# IGresupply1-2.net
KiCad netlist of a schematic drawn in Altium Designer
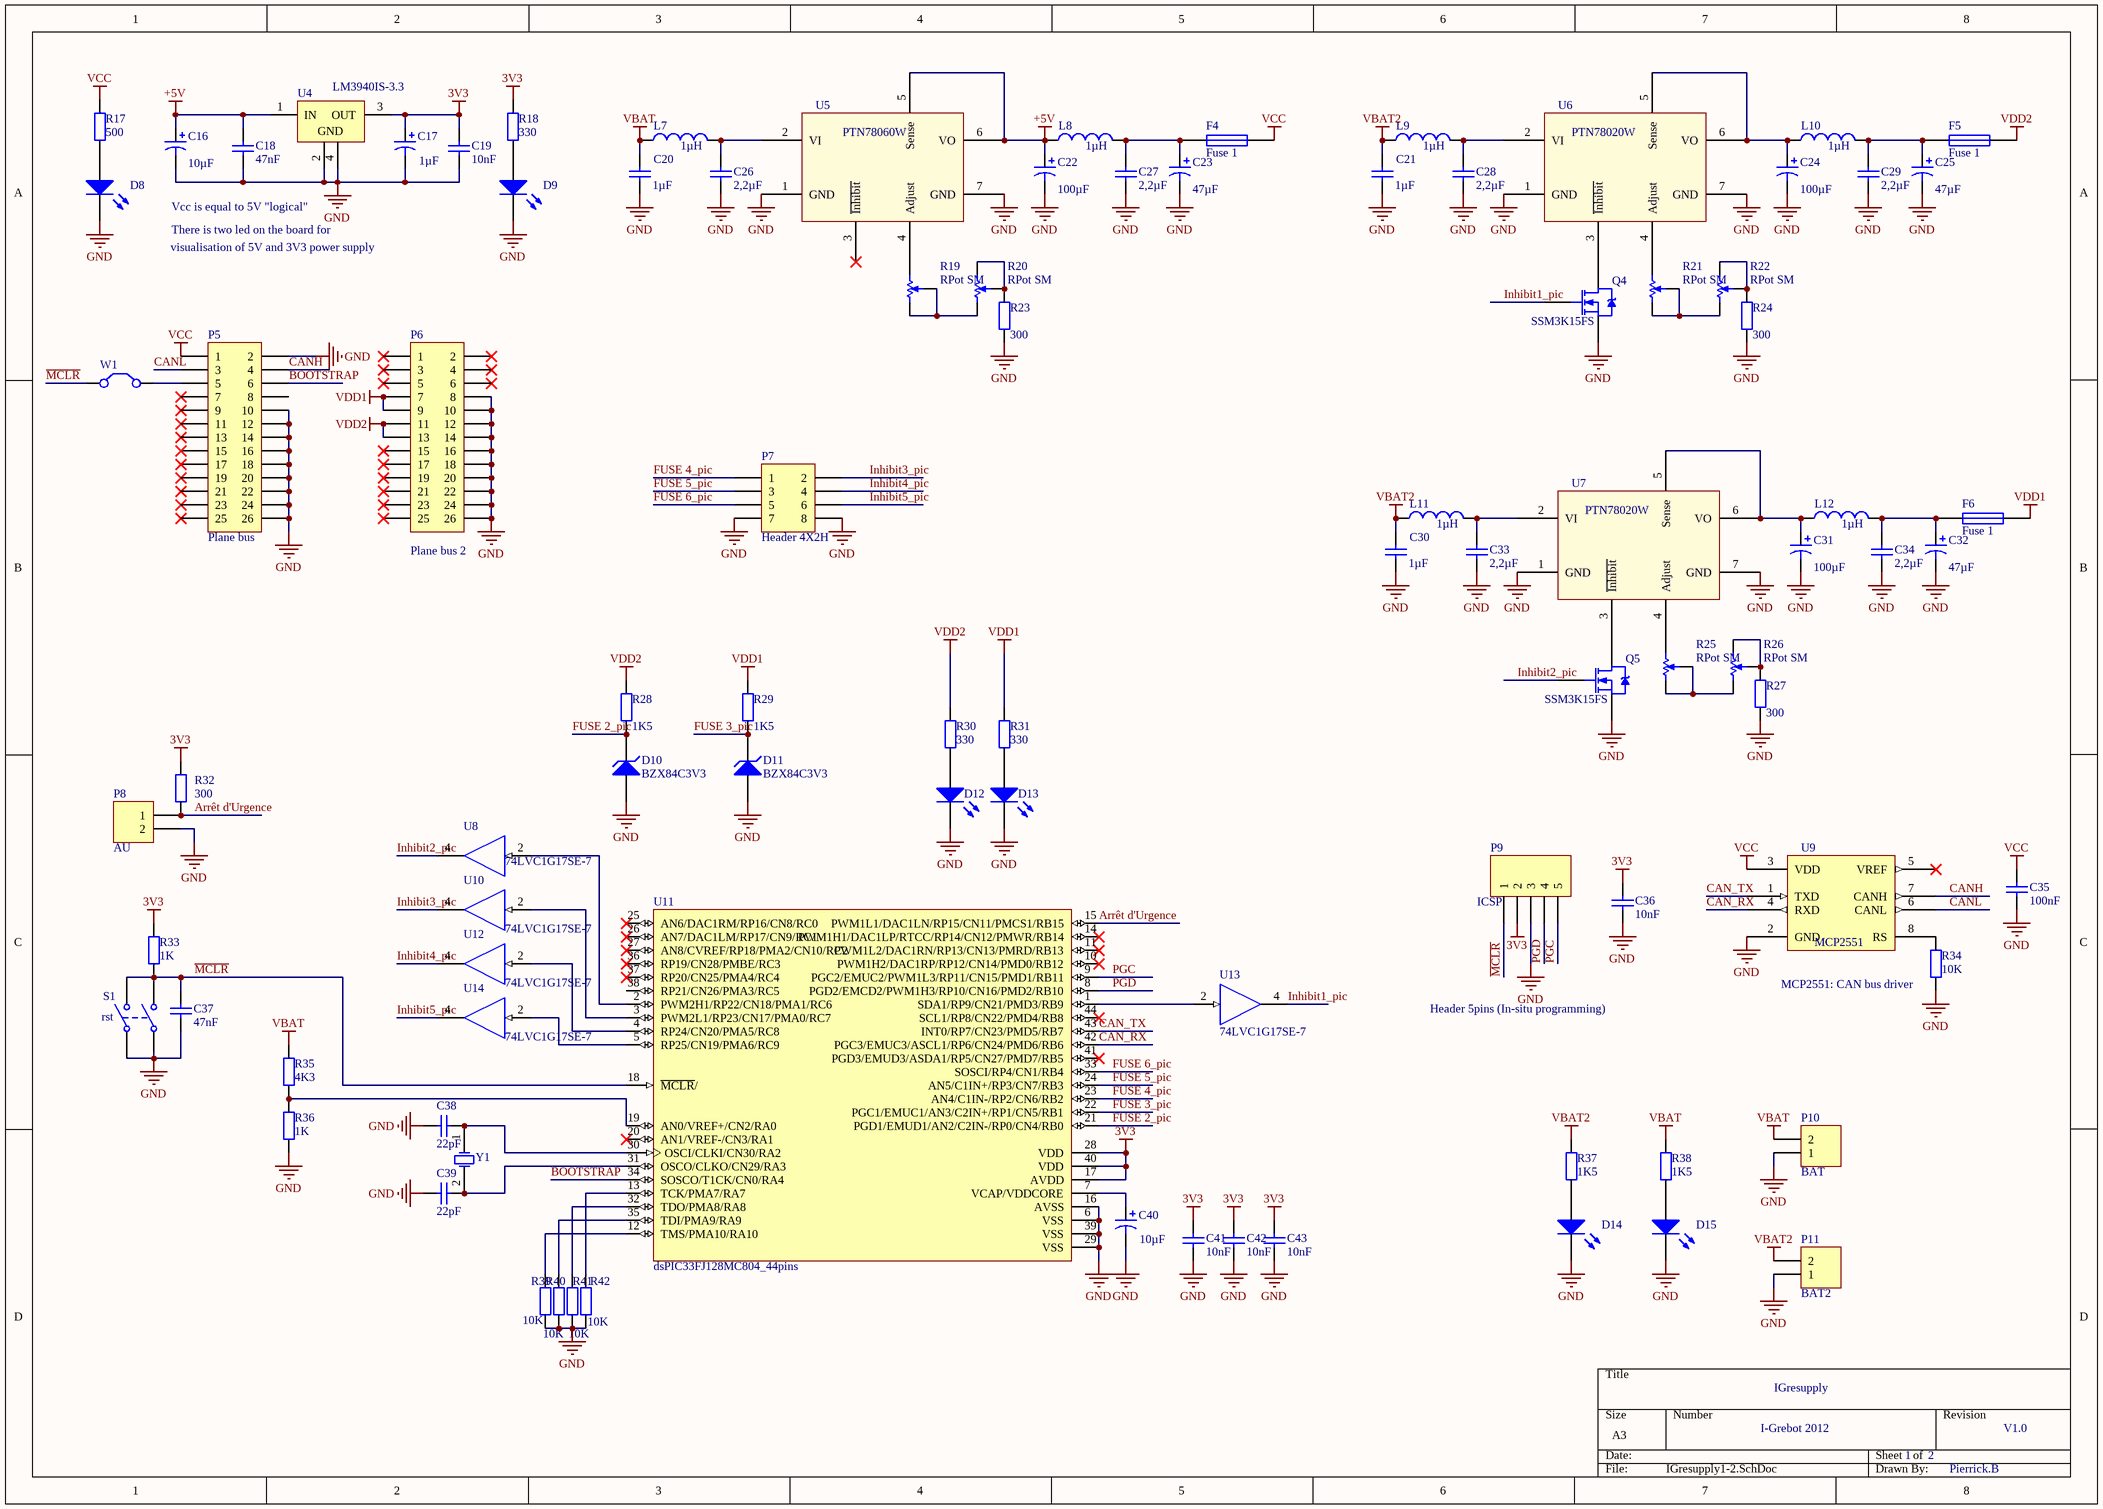
[diagram p0: IGresupply1-2.SchDoc]

(export (version "E")
  (design (tool "Eeschema 10.0.6"))
  (components
    (comp (ref "C16")
      (value "10µF")
      (footprint "Boitier tantale A")
      (description "Polarized Capacitor")
      (fields (field (name "Comment") "Cap Pol") (field (name "PUBLISHER") "Altium Limited"))
      (libsource (lib "I-GREBOT 2009") (part "Cap Pol"))
    )
    (comp (ref "C17")
      (value "1µF")
      (footprint "Boitier tantale A")
      (description "Polarized Capacitor")
      (fields (field (name "Comment") "Cap Pol") (field (name "PUBLISHER") "Altium Limited"))
      (libsource (lib "*") (part "Cap Pol"))
    )
    (comp (ref "C18")
      (value "47nF")
      (footprint "C0603")
      (description "Capacitor")
      (fields (field (name "Comment") "Cap") (field (name "PUBLISHER") "Altium Limited"))
      (libsource (lib "Miscellaneous Devices") (part "Cap"))
    )
    (comp (ref "C19")
      (value "10nF")
      (footprint "C0603")
      (description "Capacitor")
      (fields (field (name "Comment") "Cap") (field (name "PUBLISHER") "Altium Limited"))
      (libsource (lib "Miscellaneous Devices") (part "Cap"))
    )
    (comp (ref "C20")
      (value "1µF")
      (footprint "Boitier tantale A")
      (description "Capacitor")
      (fields (field (name "Comment") "Cap") (field (name "PUBLISHER") "Altium Limited"))
      (libsource (lib "LIBRARY IGREBOT") (part "Cap"))
    )
    (comp (ref "C21")
      (value "1µF")
      (footprint "Boitier tantale A")
      (description "Capacitor")
      (fields (field (name "Comment") "Cap") (field (name "PUBLISHER") "Altium Limited"))
      (libsource (lib "LIBRARY IGREBOT") (part "Cap"))
    )
    (comp (ref "C22")
      (value "100µF")
      (footprint "Boitier tantale C")
      (description "Polarized Capacitor")
      (fields (field (name "Comment") "Cap Pol") (field (name "PUBLISHER") "Altium Limited"))
      (libsource (lib "LIBRARY IGREBOT") (part "Cap Pol"))
    )
    (comp (ref "C23")
      (value "47µF")
      (footprint "Boitier tantale C")
      (description "Polarized Capacitor")
      (fields (field (name "Comment") "Cap Pol") (field (name "PUBLISHER") "Altium Limited"))
      (libsource (lib "LIBRARY IGREBOT") (part "Cap Pol"))
    )
    (comp (ref "C24")
      (value "100µF")
      (footprint "Boitier tantale C")
      (description "Polarized Capacitor")
      (fields (field (name "Comment") "Cap Pol") (field (name "PUBLISHER") "Altium Limited"))
      (libsource (lib "LIBRARY IGREBOT") (part "Cap Pol"))
    )
    (comp (ref "C25")
      (value "47µF")
      (footprint "Boitier tantale C")
      (description "Polarized Capacitor")
      (fields (field (name "Comment") "Cap Pol") (field (name "PUBLISHER") "Altium Limited"))
      (libsource (lib "LIBRARY IGREBOT") (part "Cap Pol"))
    )
    (comp (ref "C26")
      (value "2,2µF")
      (footprint "Boitier tantale A")
      (description "Capacitor")
      (fields (field (name "Comment") "Cap") (field (name "PUBLISHER") "Altium Limited"))
      (libsource (lib "LIBRARY IGREBOT") (part "Cap"))
    )
    (comp (ref "C27")
      (value "2,2µF")
      (footprint "Boitier tantale A")
      (description "Capacitor")
      (fields (field (name "Comment") "Cap") (field (name "PUBLISHER") "Altium Limited"))
      (libsource (lib "LIBRARY IGREBOT") (part "Cap"))
    )
    (comp (ref "C28")
      (value "2,2µF")
      (footprint "Boitier tantale A")
      (description "Capacitor")
      (fields (field (name "Comment") "Cap") (field (name "PUBLISHER") "Altium Limited"))
      (libsource (lib "LIBRARY IGREBOT") (part "Cap"))
    )
    (comp (ref "C29")
      (value "2,2µF")
      (footprint "Boitier tantale A")
      (description "Capacitor")
      (fields (field (name "Comment") "Cap") (field (name "PUBLISHER") "Altium Limited"))
      (libsource (lib "LIBRARY IGREBOT") (part "Cap"))
    )
    (comp (ref "C30")
      (value "1µF")
      (footprint "Boitier tantale A")
      (description "Capacitor")
      (fields (field (name "Comment") "Cap") (field (name "PUBLISHER") "Altium Limited"))
      (libsource (lib "LIBRARY IGREBOT") (part "Cap"))
    )
    (comp (ref "C31")
      (value "100µF")
      (footprint "Boitier tantale C")
      (description "Polarized Capacitor")
      (fields (field (name "Comment") "Cap Pol") (field (name "PUBLISHER") "Altium Limited"))
      (libsource (lib "LIBRARY IGREBOT") (part "Cap Pol"))
    )
    (comp (ref "C32")
      (value "47µF")
      (footprint "Boitier tantale C")
      (description "Polarized Capacitor")
      (fields (field (name "Comment") "Cap Pol") (field (name "PUBLISHER") "Altium Limited"))
      (libsource (lib "LIBRARY IGREBOT") (part "Cap Pol"))
    )
    (comp (ref "C33")
      (value "2,2µF")
      (footprint "Boitier tantale A")
      (description "Capacitor")
      (fields (field (name "Comment") "Cap") (field (name "PUBLISHER") "Altium Limited"))
      (libsource (lib "LIBRARY IGREBOT") (part "Cap"))
    )
    (comp (ref "C34")
      (value "2,2µF")
      (footprint "Boitier tantale A")
      (description "Capacitor")
      (fields (field (name "Comment") "Cap") (field (name "PUBLISHER") "Altium Limited"))
      (libsource (lib "LIBRARY IGREBOT") (part "Cap"))
    )
    (comp (ref "C35")
      (value "100nF")
      (footprint "C0603")
      (description "Capacitor")
      (fields (field (name "Comment") "Cap") (field (name "PUBLISHER") "Altium Limited"))
      (libsource (lib "Miscellaneous Devices") (part "Cap"))
    )
    (comp (ref "C36")
      (value "10nF")
      (footprint "C0603")
      (description "Capacitor")
      (fields (field (name "Comment") "Cap") (field (name "PUBLISHER") "Altium Limited"))
      (libsource (lib "Miscellaneous Devices") (part "Cap"))
    )
    (comp (ref "C37")
      (value "47nF")
      (footprint "C0603")
      (description "Capacitor")
      (fields (field (name "Comment") "Cap") (field (name "PUBLISHER") "Altium Limited"))
      (libsource (lib "Miscellaneous Devices") (part "Cap"))
    )
    (comp (ref "C38")
      (value "22pF")
      (footprint "C0603")
      (description "Capacitor")
      (fields (field (name "Comment") "Cap") (field (name "PUBLISHER") "Altium Limited"))
      (libsource (lib "Miscellaneous Devices") (part "Cap"))
    )
    (comp (ref "C39")
      (value "22pF")
      (footprint "C0603")
      (description "Capacitor")
      (fields (field (name "Comment") "Cap") (field (name "PUBLISHER") "Altium Limited"))
      (libsource (lib "Miscellaneous Devices") (part "Cap"))
    )
    (comp (ref "C40")
      (value "10µF")
      (footprint "Boitier tantale A")
      (description "Polarized Capacitor")
      (fields (field (name "Comment") "Cap Pol") (field (name "PUBLISHER") "Altium Limited"))
      (libsource (lib "*") (part "Cap Pol"))
    )
    (comp (ref "C41")
      (value "10nF")
      (footprint "C0603")
      (description "Capacitor")
      (fields (field (name "Comment") "Cap") (field (name "PUBLISHER") "Altium Limited"))
      (libsource (lib "Miscellaneous Devices") (part "Cap"))
    )
    (comp (ref "C42")
      (value "10nF")
      (footprint "C0603")
      (description "Capacitor")
      (fields (field (name "Comment") "Cap") (field (name "PUBLISHER") "Altium Limited"))
      (libsource (lib "Miscellaneous Devices") (part "Cap"))
    )
    (comp (ref "C43")
      (value "10nF")
      (footprint "C0603")
      (description "Capacitor")
      (fields (field (name "Comment") "Cap") (field (name "PUBLISHER") "Altium Limited"))
      (libsource (lib "Miscellaneous Devices") (part "Cap"))
    )
    (comp (ref "D8")
      (value "LED1")
      (footprint "HSMS-C110")
      (description "Typical RED GaAs LED")
      (fields (field (name "PUBLISHER") "Altium Limited"))
      (libsource (lib "I-GREBOT 2009") (part "LED1"))
    )
    (comp (ref "D9")
      (value "LED1")
      (footprint "HSMS-C110")
      (description "Typical RED GaAs LED")
      (fields (field (name "PUBLISHER") "Altium Limited"))
      (libsource (lib "I-GREBOT 2009") (part "LED1"))
    )
    (comp (ref "D10")
      (value "BZX84C3V3")
      (footprint "SOT-23")
      (description "Zener Diode")
      (fields (field (name "PUBLISHER") "Altium Limited"))
      (libsource (lib "LIBRARY IGREBOT") (part "D Zener"))
    )
    (comp (ref "D11")
      (value "BZX84C3V3")
      (footprint "SOT-23")
      (description "Zener Diode")
      (fields (field (name "PUBLISHER") "Altium Limited"))
      (libsource (lib "LIBRARY IGREBOT") (part "D Zener"))
    )
    (comp (ref "D12")
      (value "LED1")
      (footprint "HSMS-C110")
      (description "Typical RED GaAs LED")
      (fields (field (name "PUBLISHER") "Altium Limited"))
      (libsource (lib "I-GREBOT 2009") (part "LED1"))
    )
    (comp (ref "D13")
      (value "LED1")
      (footprint "HSMS-C110")
      (description "Typical RED GaAs LED")
      (fields (field (name "PUBLISHER") "Altium Limited"))
      (libsource (lib "I-GREBOT 2009") (part "LED1"))
    )
    (comp (ref "D14")
      (value "LED1")
      (footprint "HSMS-C110")
      (description "Typical RED GaAs LED")
      (fields (field (name "PUBLISHER") "Altium Limited"))
      (libsource (lib "I-GREBOT 2009") (part "LED1"))
    )
    (comp (ref "D15")
      (value "LED1")
      (footprint "HSMS-C110")
      (description "Typical RED GaAs LED")
      (fields (field (name "PUBLISHER") "Altium Limited"))
      (libsource (lib "I-GREBOT 2009") (part "LED1"))
    )
    (comp (ref "F4")
      (value "Fuse 1")
      (footprint "MCCQ-122")
      (description "Fuse")
      (fields (field (name "PUBLISHER") "Altium Limited"))
      (libsource (lib "LIBRARY IGREBOT") (part "Fuse 1"))
    )
    (comp (ref "F5")
      (value "Fuse 1")
      (footprint "MCCQ-122")
      (description "Fuse")
      (fields (field (name "PUBLISHER") "Altium Limited"))
      (libsource (lib "LIBRARY IGREBOT") (part "Fuse 1"))
    )
    (comp (ref "F6")
      (value "Fuse 1")
      (footprint "MCCQ-122")
      (description "Fuse")
      (fields (field (name "PUBLISHER") "Altium Limited"))
      (libsource (lib "LIBRARY IGREBOT") (part "Fuse 1"))
    )
    (comp (ref "L7")
      (value "1µH")
      (footprint "744772010")
      (description "Inductor")
      (fields (field (name "PUBLISHER") "Altium Limited"))
      (libsource (lib "LIBRARY IGREBOT") (part "Inductor"))
    )
    (comp (ref "L8")
      (value "1µH")
      (footprint "744772010")
      (description "Inductor")
      (fields (field (name "PUBLISHER") "Altium Limited"))
      (libsource (lib "LIBRARY IGREBOT") (part "Inductor"))
    )
    (comp (ref "L9")
      (value "1µH")
      (footprint "744772010")
      (description "Inductor")
      (fields (field (name "PUBLISHER") "Altium Limited"))
      (libsource (lib "LIBRARY IGREBOT") (part "Inductor"))
    )
    (comp (ref "L10")
      (value "1µH")
      (footprint "744772010")
      (description "Inductor")
      (fields (field (name "PUBLISHER") "Altium Limited"))
      (libsource (lib "LIBRARY IGREBOT") (part "Inductor"))
    )
    (comp (ref "L11")
      (value "1µH")
      (footprint "744772010")
      (description "Inductor")
      (fields (field (name "PUBLISHER") "Altium Limited"))
      (libsource (lib "LIBRARY IGREBOT") (part "Inductor"))
    )
    (comp (ref "L12")
      (value "1µH")
      (footprint "744772010")
      (description "Inductor")
      (fields (field (name "PUBLISHER") "Altium Limited"))
      (libsource (lib "LIBRARY IGREBOT") (part "Inductor"))
    )
    (comp (ref "P5")
      (value "Plane bus")
      (footprint "HDR2X13H")
      (description "Header, 13-Pin, Dual row, Right Angle")
      (fields (field (name "PUBLISHER") "Altium Limited"))
      (libsource (lib "Miscellaneous Connectors") (part "Header 13X2H"))
    )
    (comp (ref "P6")
      (value "Plane bus 2")
      (footprint "HDR2X13H")
      (description "Header, 13-Pin, Dual row, Right Angle")
      (fields (field (name "PUBLISHER") "Altium Limited"))
      (libsource (lib "Miscellaneous Connectors") (part "Header 13X2H"))
    )
    (comp (ref "P7")
      (value "Header 4X2H")
      (footprint "HDR2X4H")
      (description "Header, 4-Pin, Dual row, Right Angle")
      (fields (field (name "PUBLISHER") "Altium Limited"))
      (libsource (lib "Miscellaneous Connectors") (part "Header 4X2H"))
    )
    (comp (ref "P8")
      (value "AU")
      (footprint "SL 5.08/90")
      (description "Micro-Fit, 3.0")
      (fields (field (name "PUBLISHER") "Altium Limited"))
      (libsource (lib "") (part "0436500203_1"))
    )
    (comp (ref "P9")
      (value "ICSP")
      (footprint "HDR1X5")
      (description "Header, 5-Pin")
      (fields (field (name "PUBLISHER") "Altium Limited"))
      (libsource (lib "LIBRARY IGREBOT") (part "Header 5"))
    )
    (comp (ref "P10")
      (value "BAT")
      (footprint "SL 5.08/90")
      (description "Micro-Fit, 3.0")
      (fields (field (name "PUBLISHER") "Altium Limited"))
      (libsource (lib "I-GREBOT 2010") (part "0436500203"))
    )
    (comp (ref "P11")
      (value "BAT2")
      (footprint "SL 5.08/90")
      (description "Micro-Fit, 3.0")
      (fields (field (name "PUBLISHER") "Altium Limited"))
      (libsource (lib "I-GREBOT 2010") (part "0436500203"))
    )
    (comp (ref "Q4")
      (value "SSM3K15FS")
      (footprint "SOT-23")
      (description "N-Channel Power MOSFET")
      (fields (field (name "PUBLISHER") "Altium Limited"))
      (libsource (lib "LIBRARY IGREBOT") (part "NMOS-2"))
    )
    (comp (ref "Q5")
      (value "SSM3K15FS")
      (footprint "SOT-23")
      (description "N-Channel Power MOSFET")
      (fields (field (name "PUBLISHER") "Altium Limited"))
      (libsource (lib "LIBRARY IGREBOT") (part "NMOS-2"))
    )
    (comp (ref "R17")
      (value "500")
      (footprint "0805")
      (description "Resistor")
      (fields (field (name "Comment") "Res2") (field (name "PUBLISHER") "Altium Limited"))
      (libsource (lib "*") (part "Res2"))
    )
    (comp (ref "R18")
      (value "330")
      (footprint "0805")
      (description "Resistor")
      (fields (field (name "Comment") "Res2") (field (name "PUBLISHER") "Altium Limited"))
      (libsource (lib "*") (part "Res2"))
    )
    (comp (ref "R19")
      (value "RPot SM")
      (footprint "3296X")
      (description "Square Trimming Potentiometer")
      (fields (field (name "PUBLISHER") "Altium Limited"))
      (libsource (lib "LIBRARY IGREBOT") (part "RPot SM"))
    )
    (comp (ref "R20")
      (value "RPot SM")
      (footprint "3296X")
      (description "Square Trimming Potentiometer")
      (fields (field (name "PUBLISHER") "Altium Limited"))
      (libsource (lib "LIBRARY IGREBOT") (part "RPot SM"))
    )
    (comp (ref "R21")
      (value "RPot SM")
      (footprint "3296X")
      (description "Square Trimming Potentiometer")
      (fields (field (name "PUBLISHER") "Altium Limited"))
      (libsource (lib "LIBRARY IGREBOT") (part "RPot SM"))
    )
    (comp (ref "R22")
      (value "RPot SM")
      (footprint "3296X")
      (description "Square Trimming Potentiometer")
      (fields (field (name "PUBLISHER") "Altium Limited"))
      (libsource (lib "LIBRARY IGREBOT") (part "RPot SM"))
    )
    (comp (ref "R23")
      (value "300")
      (footprint "0805")
      (description "Resistor")
      (fields (field (name "Comment") "Res2") (field (name "PUBLISHER") "Altium Limited"))
      (libsource (lib "LIBRARY IGREBOT") (part "Res2"))
    )
    (comp (ref "R24")
      (value "300")
      (footprint "0805")
      (description "Resistor")
      (fields (field (name "Comment") "Res2") (field (name "PUBLISHER") "Altium Limited"))
      (libsource (lib "LIBRARY IGREBOT") (part "Res2"))
    )
    (comp (ref "R25")
      (value "RPot SM")
      (footprint "3296X")
      (description "Square Trimming Potentiometer")
      (fields (field (name "PUBLISHER") "Altium Limited"))
      (libsource (lib "LIBRARY IGREBOT") (part "RPot SM"))
    )
    (comp (ref "R26")
      (value "RPot SM")
      (footprint "3296X")
      (description "Square Trimming Potentiometer")
      (fields (field (name "PUBLISHER") "Altium Limited"))
      (libsource (lib "LIBRARY IGREBOT") (part "RPot SM"))
    )
    (comp (ref "R27")
      (value "300")
      (footprint "0805")
      (description "Resistor")
      (fields (field (name "Comment") "Res2") (field (name "PUBLISHER") "Altium Limited"))
      (libsource (lib "LIBRARY IGREBOT") (part "Res2"))
    )
    (comp (ref "R28")
      (value "1K5")
      (footprint "0805")
      (description "Resistor")
      (fields (field (name "Comment") "Res2") (field (name "PUBLISHER") "Altium Limited"))
      (libsource (lib "LIBRARY IGREBOT") (part "Res2"))
    )
    (comp (ref "R29")
      (value "1K5")
      (footprint "0805")
      (description "Resistor")
      (fields (field (name "Comment") "Res2") (field (name "PUBLISHER") "Altium Limited"))
      (libsource (lib "LIBRARY IGREBOT") (part "Res2"))
    )
    (comp (ref "R30")
      (value "330")
      (footprint "0805")
      (description "Resistor")
      (fields (field (name "Comment") "Res2") (field (name "PUBLISHER") "Altium Limited"))
      (libsource (lib "*") (part "Res2"))
    )
    (comp (ref "R31")
      (value "330")
      (footprint "0805")
      (description "Resistor")
      (fields (field (name "Comment") "Res2") (field (name "PUBLISHER") "Altium Limited"))
      (libsource (lib "*") (part "Res2"))
    )
    (comp (ref "R32")
      (value "300")
      (footprint "0603")
      (description "Resistor")
      (fields (field (name "Comment") "Res2") (field (name "PUBLISHER") "Altium Limited"))
      (libsource (lib "LIBRARY IGREBOT") (part "Res2"))
    )
    (comp (ref "R33")
      (value "1K")
      (footprint "0603")
      (description "Resistor")
      (fields (field (name "Comment") "Res2") (field (name "PUBLISHER") "Altium Limited"))
      (libsource (lib "*") (part "Res2"))
    )
    (comp (ref "R34")
      (value "10K")
      (footprint "0805")
      (description "Resistor")
      (fields (field (name "Comment") "Res2") (field (name "PUBLISHER") "Altium Limited"))
      (libsource (lib "") (part "Res2_1"))
    )
    (comp (ref "R35")
      (value "4K3")
      (footprint "0603")
      (description "Resistor")
      (fields (field (name "Comment") "Res2") (field (name "PUBLISHER") "Altium Limited"))
      (libsource (lib "*") (part "Res2"))
    )
    (comp (ref "R36")
      (value "1K")
      (footprint "0603")
      (description "Resistor")
      (fields (field (name "Comment") "Res2") (field (name "PUBLISHER") "Altium Limited"))
      (libsource (lib "*") (part "Res2"))
    )
    (comp (ref "R37")
      (value "1K5")
      (footprint "0805")
      (description "Resistor")
      (fields (field (name "Comment") "Res2") (field (name "PUBLISHER") "Altium Limited"))
      (libsource (lib "*") (part "Res2"))
    )
    (comp (ref "R38")
      (value "1K5")
      (footprint "0805")
      (description "Resistor")
      (fields (field (name "Comment") "Res2") (field (name "PUBLISHER") "Altium Limited"))
      (libsource (lib "*") (part "Res2"))
    )
    (comp (ref "R39")
      (value "10K")
      (footprint "0603")
      (description "Resistor")
      (fields (field (name "Comment") "Res2") (field (name "PUBLISHER") "Altium Limited"))
      (libsource (lib "*") (part "Res2"))
    )
    (comp (ref "R40")
      (value "10K")
      (footprint "0603")
      (description "Resistor")
      (fields (field (name "Comment") "Res2") (field (name "PUBLISHER") "Altium Limited"))
      (libsource (lib "*") (part "Res2"))
    )
    (comp (ref "R41")
      (value "10K")
      (footprint "0603")
      (description "Resistor")
      (fields (field (name "Comment") "Res2") (field (name "PUBLISHER") "Altium Limited"))
      (libsource (lib "*") (part "Res2"))
    )
    (comp (ref "R42")
      (value "10K")
      (footprint "0603")
      (description "Resistor")
      (fields (field (name "Comment") "Res2") (field (name "PUBLISHER") "Altium Limited"))
      (libsource (lib "*") (part "Res2"))
    )
    (comp (ref "S1")
      (value "rst")
      (footprint "Bouton poussoir")
      (description "Double-Pole, Single-Throw Switch")
      (fields (field (name "PUBLISHER") "Altium Limited"))
      (libsource (lib "*") (part "SW-DPST"))
    )
    (comp (ref "U4")
      (value "LM3940IS-3.3")
      (footprint "SOT223")
      (description "1A Low-Dropout Regulator For 5V to 3.3V Conversion")
      (fields (field (name "PUBLISHER") "Altium Limited"))
      (libsource (lib "I-GREBOT 2009") (part "LM3940IS-3.3"))
    )
    (comp (ref "U5")
      (value "PTN78060W")
      (footprint "EUW")
      (libsource (lib "LIBRARY IGREBOT") (part "PTN78060W"))
    )
    (comp (ref "U6")
      (value "PTN78020W")
      (footprint "EUK")
      (libsource (lib "LIBRARY IGREBOT") (part "PTN78020W"))
    )
    (comp (ref "U7")
      (value "PTN78020W")
      (footprint "EUK")
      (libsource (lib "LIBRARY IGREBOT") (part "PTN78020W"))
    )
    (comp (ref "U8")
      (value "74LVC1G17SE-7")
      (footprint "DBV")
      (description "SINGLE BUS BUFFER GATE  WITH 3-STATE OUTPUT")
      (fields (field (name "PUBLISHER") "Altium Limited"))
      (libsource (lib "LIBRARY IGREBOT") (part "74LVC1G17SE-7"))
    )
    (comp (ref "U9")
      (value "MCP2551")
      (footprint "SOIC150-8")
      (description "High Speed Can Transceiver")
      (fields (field (name "PUBLISHER") "Altium Limited"))
      (libsource (lib "*") (part "MCP2551"))
    )
    (comp (ref "U10")
      (value "74LVC1G17SE-7")
      (footprint "DBV")
      (description "SINGLE BUS BUFFER GATE  WITH 3-STATE OUTPUT")
      (fields (field (name "PUBLISHER") "Altium Limited"))
      (libsource (lib "LIBRARY IGREBOT") (part "74LVC1G17SE-7"))
    )
    (comp (ref "U11")
      (value "dsPIC33FJ128MC804_44pins")
      (footprint "TQFP-44")
      (libsource (lib "I-GREBOT 2009") (part "dsPIC33FJ128MC804_44pins"))
    )
    (comp (ref "U12")
      (value "74LVC1G17SE-7")
      (footprint "DBV")
      (description "SINGLE BUS BUFFER GATE  WITH 3-STATE OUTPUT")
      (fields (field (name "PUBLISHER") "Altium Limited"))
      (libsource (lib "LIBRARY IGREBOT") (part "74LVC1G17SE-7"))
    )
    (comp (ref "U13")
      (value "74LVC1G17SE-7")
      (footprint "DBV")
      (description "SINGLE BUS BUFFER GATE  WITH 3-STATE OUTPUT")
      (fields (field (name "PUBLISHER") "Altium Limited"))
      (libsource (lib "LIBRARY IGREBOT") (part "74LVC1G17SE-7"))
    )
    (comp (ref "U14")
      (value "74LVC1G17SE-7")
      (footprint "DBV")
      (description "SINGLE BUS BUFFER GATE  WITH 3-STATE OUTPUT")
      (fields (field (name "PUBLISHER") "Altium Limited"))
      (libsource (lib "LIBRARY IGREBOT") (part "74LVC1G17SE-7"))
    )
    (comp (ref "W1")
      (value "Jumper")
      (footprint "HDR1X2")
      (description "Jumper Wire")
      (fields (field (name "PUBLISHER") "Altium Limited"))
      (libsource (lib "LIBRARY IGREBOT") (part "Jumper"))
    )
    (comp (ref "Y1")
      (value "XTAL")
      (footprint "HC49US")
      (description "Crystal Oscillator")
      (fields (field (name "PUBLISHER") "Altium Limited"))
      (libsource (lib "*") (part "XTAL"))
    )
  )
  (nets
    (net (code "1") (name "+5V") (class "Default")
      (node (ref "C16") (pin "1") (pinfunction "1_1") (pintype "passive"))
      (node (ref "C18") (pin "2") (pinfunction "2_2") (pintype "passive"))
      (node (ref "C22") (pin "1") (pinfunction "1_1") (pintype "passive"))
      (node (ref "L8") (pin "1") (pinfunction "1_1") (pintype "passive"))
      (node (ref "U10") (pin "5") (pinfunction "+5V_5") (pintype "power_in"))
      (node (ref "U12") (pin "5") (pinfunction "+5V_5") (pintype "power_in"))
      (node (ref "U13") (pin "5") (pinfunction "+5V_5") (pintype "power_in"))
      (node (ref "U14") (pin "5") (pinfunction "+5V_5") (pintype "power_in"))
      (node (ref "U4") (pin "1") (pinfunction "IN_1") (pintype "power_in"))
      (node (ref "U5") (pin "5") (pinfunction "Sense_5") (pintype "power_in"))
      (node (ref "U5") (pin "6") (pinfunction "VO_6") (pintype "power_in"))
      (node (ref "U8") (pin "5") (pinfunction "+5V_5") (pintype "power_in"))
    )
    (net (code "2") (name "/Arrêt d'Urgence") (class "Default")
      (node (ref "P8") (pin "1") (pinfunction "1_1") (pintype "passive"))
      (node (ref "R32") (pin "1") (pinfunction "1_1") (pintype "passive"))
      (node (ref "U11") (pin "15") (pinfunction "PWM1L1/DAC1LN/RP15/CN11/PMCS1/RB15_15") (pintype "bidirectional"))
    )
    (net (code "3") (name "/BOOTSTRAP") (class "Default")
      (node (ref "P5") (pin "6") (pinfunction "6_6") (pintype "passive"))
      (node (ref "U11") (pin "34") (pinfunction "SOSCO/T1CK/CN0/RA4_34") (pintype "bidirectional"))
    )
    (net (code "4") (name "/CANH") (class "Default")
      (node (ref "P5") (pin "4") (pinfunction "4_4") (pintype "passive"))
      (node (ref "U9") (pin "7") (pinfunction "CANH_7") (pintype "output"))
    )
    (net (code "5") (name "/CANL") (class "Default")
      (node (ref "P5") (pin "3") (pinfunction "3_3") (pintype "passive"))
      (node (ref "U9") (pin "6") (pinfunction "CANL_6") (pintype "output"))
    )
    (net (code "6") (name "/CAN_RX") (class "Default")
      (node (ref "U11") (pin "42") (pinfunction "PGC3/EMUC3/ASCL1/RP6/CN24/PMD6/RB6_42") (pintype "bidirectional"))
      (node (ref "U9") (pin "4") (pinfunction "RXD_4") (pintype "output"))
    )
    (net (code "7") (name "/CAN_TX") (class "Default")
      (node (ref "U11") (pin "43") (pinfunction "INT0/RP7/CN23/PMD5/RB7_43") (pintype "bidirectional"))
      (node (ref "U9") (pin "1") (pinfunction "TXD_1") (pintype "input"))
    )
    (net (code "8") (name "/FUSE 2_pic") (class "Default")
      (node (ref "D10") (pin "3") (pinfunction "K_3") (pintype "passive"))
      (node (ref "R28") (pin "1") (pinfunction "1_1") (pintype "passive"))
      (node (ref "U11") (pin "21") (pinfunction "PGD1/EMUD1/AN2/C2IN-/RP0/CN4/RB0_21") (pintype "bidirectional"))
    )
    (net (code "9") (name "/FUSE 3_pic") (class "Default")
      (node (ref "D11") (pin "3") (pinfunction "K_3") (pintype "passive"))
      (node (ref "R29") (pin "1") (pinfunction "1_1") (pintype "passive"))
      (node (ref "U11") (pin "22") (pinfunction "PGC1/EMUC1/AN3/C2IN+/RP1/CN5/RB1_22") (pintype "bidirectional"))
    )
    (net (code "10") (name "/FUSE 4_pic") (class "Default")
      (node (ref "P7") (pin "1") (pinfunction "1_1") (pintype "passive"))
      (node (ref "U11") (pin "23") (pinfunction "AN4/C1IN-/RP2/CN6/RB2_23") (pintype "bidirectional"))
    )
    (net (code "11") (name "/FUSE 5_pic") (class "Default")
      (node (ref "P7") (pin "3") (pinfunction "3_3") (pintype "passive"))
      (node (ref "U11") (pin "24") (pinfunction "AN5/C1IN+/RP3/CN7/RB3_24") (pintype "bidirectional"))
    )
    (net (code "12") (name "/FUSE 6_pic") (class "Default")
      (node (ref "P7") (pin "5") (pinfunction "5_5") (pintype "passive"))
      (node (ref "U11") (pin "33") (pinfunction "SOSCI/RP4/CN1/RB4_33") (pintype "bidirectional"))
    )
    (net (code "13") (name "/Inhibit1_pic") (class "Default")
      (node (ref "Q4") (pin "1") (pinfunction "G_1") (pintype "passive"))
      (node (ref "U13") (pin "4") (pinfunction "Y_4") (pintype "tri_state"))
    )
    (net (code "14") (name "/Inhibit2_pic") (class "Default")
      (node (ref "Q5") (pin "1") (pinfunction "G_1") (pintype "passive"))
      (node (ref "U8") (pin "4") (pinfunction "Y_4") (pintype "tri_state"))
    )
    (net (code "15") (name "/Inhibit3_pic") (class "Default")
      (node (ref "P7") (pin "2") (pinfunction "2_2") (pintype "passive"))
      (node (ref "U10") (pin "4") (pinfunction "Y_4") (pintype "tri_state"))
    )
    (net (code "16") (name "/Inhibit4_pic") (class "Default")
      (node (ref "P7") (pin "4") (pinfunction "4_4") (pintype "passive"))
      (node (ref "U12") (pin "4") (pinfunction "Y_4") (pintype "tri_state"))
    )
    (net (code "17") (name "/Inhibit5_pic") (class "Default")
      (node (ref "P7") (pin "6") (pinfunction "6_6") (pintype "passive"))
      (node (ref "U14") (pin "4") (pinfunction "Y_4") (pintype "tri_state"))
    )
    (net (code "18") (name "/PGC") (class "Default")
      (node (ref "P9") (pin "5") (pinfunction "5_5") (pintype "passive"))
      (node (ref "U11") (pin "9") (pinfunction "PGC2/EMUC2/PWM1L3/RP11/CN15/PMD1/RB11_9") (pintype "bidirectional"))
    )
    (net (code "19") (name "/PGD") (class "Default")
      (node (ref "P9") (pin "4") (pinfunction "4_4") (pintype "passive"))
      (node (ref "U11") (pin "8") (pinfunction "PGD2/EMCD2/PWM1H3/RP10/CN16/PMD2/RB10_8") (pintype "bidirectional"))
    )
    (net (code "20") (name "/~{MCLR}") (class "Default")
      (node (ref "C37") (pin "2") (pinfunction "2_2") (pintype "passive"))
      (node (ref "P9") (pin "1") (pinfunction "1_1") (pintype "passive"))
      (node (ref "R33") (pin "1") (pinfunction "1_1") (pintype "passive"))
      (node (ref "S1") (pin "2") (pinfunction "NO1_2") (pintype "passive"))
      (node (ref "S1") (pin "4") (pinfunction "NO2_4") (pintype "passive"))
      (node (ref "U11") (pin "18") (pinfunction "~{MCLR}/_18") (pintype "input"))
      (node (ref "W1") (pin "1") (pinfunction "C1_1") (pintype "passive"))
    )
    (net (code "21") (name "3V3") (class "Default")
      (node (ref "C17") (pin "1") (pinfunction "1_1") (pintype "passive"))
      (node (ref "C19") (pin "2") (pinfunction "2_2") (pintype "passive"))
      (node (ref "C36") (pin "2") (pinfunction "2_2") (pintype "passive"))
      (node (ref "C41") (pin "2") (pinfunction "2_2") (pintype "passive"))
      (node (ref "C42") (pin "2") (pinfunction "2_2") (pintype "passive"))
      (node (ref "C43") (pin "2") (pinfunction "2_2") (pintype "passive"))
      (node (ref "P9") (pin "2") (pinfunction "2_2") (pintype "passive"))
      (node (ref "R18") (pin "2") (pinfunction "2_2") (pintype "passive"))
      (node (ref "R32") (pin "2") (pinfunction "2_2") (pintype "passive"))
      (node (ref "R33") (pin "2") (pinfunction "2_2") (pintype "passive"))
      (node (ref "U11") (pin "17") (pinfunction "AVDD_17") (pintype "power_in"))
      (node (ref "U11") (pin "28") (pinfunction "VDD_28") (pintype "power_in"))
      (node (ref "U11") (pin "40") (pinfunction "VDD_40") (pintype "power_in"))
      (node (ref "U4") (pin "3") (pinfunction "OUT_3") (pintype "power_in"))
    )
    (net (code "22") (name "GND") (class "Default")
      (node (ref "C16") (pin "2") (pinfunction "2_2") (pintype "passive"))
      (node (ref "C17") (pin "2") (pinfunction "2_2") (pintype "passive"))
      (node (ref "C18") (pin "1") (pinfunction "1_1") (pintype "passive"))
      (node (ref "C19") (pin "1") (pinfunction "1_1") (pintype "passive"))
      (node (ref "C20") (pin "1") (pinfunction "1_1") (pintype "passive"))
      (node (ref "C21") (pin "1") (pinfunction "1_1") (pintype "passive"))
      (node (ref "C22") (pin "2") (pinfunction "2_2") (pintype "passive"))
      (node (ref "C23") (pin "2") (pinfunction "2_2") (pintype "passive"))
      (node (ref "C24") (pin "2") (pinfunction "2_2") (pintype "passive"))
      (node (ref "C25") (pin "2") (pinfunction "2_2") (pintype "passive"))
      (node (ref "C26") (pin "1") (pinfunction "1_1") (pintype "passive"))
      (node (ref "C27") (pin "1") (pinfunction "1_1") (pintype "passive"))
      (node (ref "C28") (pin "1") (pinfunction "1_1") (pintype "passive"))
      (node (ref "C29") (pin "1") (pinfunction "1_1") (pintype "passive"))
      (node (ref "C30") (pin "1") (pinfunction "1_1") (pintype "passive"))
      (node (ref "C31") (pin "2") (pinfunction "2_2") (pintype "passive"))
      (node (ref "C32") (pin "2") (pinfunction "2_2") (pintype "passive"))
      (node (ref "C33") (pin "1") (pinfunction "1_1") (pintype "passive"))
      (node (ref "C34") (pin "1") (pinfunction "1_1") (pintype "passive"))
      (node (ref "C35") (pin "1") (pinfunction "1_1") (pintype "passive"))
      (node (ref "C36") (pin "1") (pinfunction "1_1") (pintype "passive"))
      (node (ref "C37") (pin "1") (pinfunction "1_1") (pintype "passive"))
      (node (ref "C38") (pin "1") (pinfunction "1_1") (pintype "passive"))
      (node (ref "C39") (pin "1") (pinfunction "1_1") (pintype "passive"))
      (node (ref "C40") (pin "2") (pinfunction "2_2") (pintype "passive"))
      (node (ref "C41") (pin "1") (pinfunction "1_1") (pintype "passive"))
      (node (ref "C42") (pin "1") (pinfunction "1_1") (pintype "passive"))
      (node (ref "C43") (pin "1") (pinfunction "1_1") (pintype "passive"))
      (node (ref "D10") (pin "1") (pinfunction "A_1") (pintype "passive"))
      (node (ref "D11") (pin "1") (pinfunction "A_1") (pintype "passive"))
      (node (ref "D12") (pin "2") (pinfunction "K_2") (pintype "passive"))
      (node (ref "D13") (pin "2") (pinfunction "K_2") (pintype "passive"))
      (node (ref "D14") (pin "2") (pinfunction "K_2") (pintype "passive"))
      (node (ref "D15") (pin "2") (pinfunction "K_2") (pintype "passive"))
      (node (ref "D8") (pin "2") (pinfunction "K_2") (pintype "passive"))
      (node (ref "D9") (pin "2") (pinfunction "K_2") (pintype "passive"))
      (node (ref "P10") (pin "1") (pinfunction "1_1") (pintype "passive"))
      (node (ref "P11") (pin "1") (pinfunction "1_1") (pintype "passive"))
      (node (ref "P5") (pin "10") (pinfunction "10_10") (pintype "passive"))
      (node (ref "P5") (pin "12") (pinfunction "12_12") (pintype "passive"))
      (node (ref "P5") (pin "14") (pinfunction "14_14") (pintype "passive"))
      (node (ref "P5") (pin "16") (pinfunction "16_16") (pintype "passive"))
      (node (ref "P5") (pin "18") (pinfunction "18_18") (pintype "passive"))
      (node (ref "P5") (pin "2") (pinfunction "2_2") (pintype "passive"))
      (node (ref "P5") (pin "20") (pinfunction "20_20") (pintype "passive"))
      (node (ref "P5") (pin "22") (pinfunction "22_22") (pintype "passive"))
      (node (ref "P5") (pin "24") (pinfunction "24_24") (pintype "passive"))
      (node (ref "P5") (pin "26") (pinfunction "26_26") (pintype "passive"))
      (node (ref "P6") (pin "10") (pinfunction "10_10") (pintype "passive"))
      (node (ref "P6") (pin "12") (pinfunction "12_12") (pintype "passive"))
      (node (ref "P6") (pin "14") (pinfunction "14_14") (pintype "passive"))
      (node (ref "P6") (pin "16") (pinfunction "16_16") (pintype "passive"))
      (node (ref "P6") (pin "18") (pinfunction "18_18") (pintype "passive"))
      (node (ref "P6") (pin "20") (pinfunction "20_20") (pintype "passive"))
      (node (ref "P6") (pin "22") (pinfunction "22_22") (pintype "passive"))
      (node (ref "P6") (pin "24") (pinfunction "24_24") (pintype "passive"))
      (node (ref "P6") (pin "26") (pinfunction "26_26") (pintype "passive"))
      (node (ref "P6") (pin "8") (pinfunction "8_8") (pintype "passive"))
      (node (ref "P7") (pin "7") (pinfunction "7_7") (pintype "passive"))
      (node (ref "P7") (pin "8") (pinfunction "8_8") (pintype "passive"))
      (node (ref "P8") (pin "2") (pinfunction "2_2") (pintype "passive"))
      (node (ref "P9") (pin "3") (pinfunction "3_3") (pintype "passive"))
      (node (ref "Q4") (pin "3") (pinfunction "S_3") (pintype "passive"))
      (node (ref "Q5") (pin "3") (pinfunction "S_3") (pintype "passive"))
      (node (ref "R23") (pin "1") (pinfunction "1_1") (pintype "passive"))
      (node (ref "R24") (pin "1") (pinfunction "1_1") (pintype "passive"))
      (node (ref "R27") (pin "1") (pinfunction "1_1") (pintype "passive"))
      (node (ref "R34") (pin "1") (pinfunction "1_1") (pintype "passive"))
      (node (ref "R36") (pin "1") (pinfunction "1_1") (pintype "passive"))
      (node (ref "R39") (pin "1") (pinfunction "1_1") (pintype "passive"))
      (node (ref "R40") (pin "1") (pinfunction "1_1") (pintype "passive"))
      (node (ref "R41") (pin "1") (pinfunction "1_1") (pintype "passive"))
      (node (ref "R42") (pin "1") (pinfunction "1_1") (pintype "passive"))
      (node (ref "S1") (pin "1") (pinfunction "COMMON1_1") (pintype "passive"))
      (node (ref "S1") (pin "3") (pinfunction "COMMON2_3") (pintype "passive"))
      (node (ref "U10") (pin "3") (pinfunction "GND_3") (pintype "power_in"))
      (node (ref "U11") (pin "16") (pinfunction "AVSS_16") (pintype "power_in"))
      (node (ref "U11") (pin "29") (pinfunction "VSS_29") (pintype "power_in"))
      (node (ref "U11") (pin "39") (pinfunction "VSS_39") (pintype "power_in"))
      (node (ref "U11") (pin "6") (pinfunction "VSS_6") (pintype "power_in"))
      (node (ref "U12") (pin "3") (pinfunction "GND_3") (pintype "power_in"))
      (node (ref "U13") (pin "3") (pinfunction "GND_3") (pintype "power_in"))
      (node (ref "U14") (pin "3") (pinfunction "GND_3") (pintype "power_in"))
      (node (ref "U4") (pin "2") (pinfunction "GND_2") (pintype "power_in"))
      (node (ref "U4") (pin "4") (pinfunction "GND_4") (pintype "power_in"))
      (node (ref "U5") (pin "1") (pinfunction "GND_1") (pintype "power_in"))
      (node (ref "U5") (pin "7") (pinfunction "GND_7") (pintype "power_in"))
      (node (ref "U6") (pin "1") (pinfunction "GND_1") (pintype "power_in"))
      (node (ref "U6") (pin "7") (pinfunction "GND_7") (pintype "power_in"))
      (node (ref "U7") (pin "1") (pinfunction "GND_1") (pintype "power_in"))
      (node (ref "U7") (pin "7") (pinfunction "GND_7") (pintype "power_in"))
      (node (ref "U8") (pin "3") (pinfunction "GND_3") (pintype "power_in"))
      (node (ref "U9") (pin "2") (pinfunction "GND_2") (pintype "power_in"))
    )
    (net (code "23") (name "Net-(C23-Pad1)") (class "Default")
      (node (ref "C23") (pin "1") (pinfunction "1_1") (pintype "passive"))
      (node (ref "C27") (pin "2") (pinfunction "2_2") (pintype "passive"))
      (node (ref "F4") (pin "1") (pinfunction "1_1") (pintype "passive"))
      (node (ref "L8") (pin "2") (pinfunction "2_2") (pintype "passive"))
    )
    (net (code "24") (name "Net-(C25-Pad1)") (class "Default")
      (node (ref "C25") (pin "1") (pinfunction "1_1") (pintype "passive"))
      (node (ref "C29") (pin "2") (pinfunction "2_2") (pintype "passive"))
      (node (ref "F5") (pin "1") (pinfunction "1_1") (pintype "passive"))
      (node (ref "L10") (pin "2") (pinfunction "2_2") (pintype "passive"))
    )
    (net (code "25") (name "Net-(C32-Pad1)") (class "Default")
      (node (ref "C32") (pin "1") (pinfunction "1_1") (pintype "passive"))
      (node (ref "C34") (pin "2") (pinfunction "2_2") (pintype "passive"))
      (node (ref "F6") (pin "1") (pinfunction "1_1") (pintype "passive"))
      (node (ref "L12") (pin "2") (pinfunction "2_2") (pintype "passive"))
    )
    (net (code "26") (name "Net-(D8-A)") (class "Default")
      (node (ref "D8") (pin "1") (pinfunction "A_1") (pintype "passive"))
      (node (ref "R17") (pin "1") (pinfunction "1_1") (pintype "passive"))
    )
    (net (code "27") (name "Net-(D9-A)") (class "Default")
      (node (ref "D9") (pin "1") (pinfunction "A_1") (pintype "passive"))
      (node (ref "R18") (pin "1") (pinfunction "1_1") (pintype "passive"))
    )
    (net (code "28") (name "Net-(D12-A)") (class "Default")
      (node (ref "D12") (pin "1") (pinfunction "A_1") (pintype "passive"))
      (node (ref "R30") (pin "1") (pinfunction "1_1") (pintype "passive"))
    )
    (net (code "29") (name "Net-(D13-A)") (class "Default")
      (node (ref "D13") (pin "1") (pinfunction "A_1") (pintype "passive"))
      (node (ref "R31") (pin "1") (pinfunction "1_1") (pintype "passive"))
    )
    (net (code "30") (name "Net-(D14-A)") (class "Default")
      (node (ref "D14") (pin "1") (pinfunction "A_1") (pintype "passive"))
      (node (ref "R37") (pin "1") (pinfunction "1_1") (pintype "passive"))
    )
    (net (code "31") (name "Net-(D15-A)") (class "Default")
      (node (ref "D15") (pin "1") (pinfunction "A_1") (pintype "passive"))
      (node (ref "R38") (pin "1") (pinfunction "1_1") (pintype "passive"))
    )
    (net (code "32") (name "Net-(Q4-D)") (class "Default")
      (node (ref "Q4") (pin "2") (pinfunction "D_2") (pintype "passive"))
      (node (ref "U6") (pin "3") (pinfunction "~{Inhibit}_3") (pintype "power_in"))
    )
    (net (code "33") (name "Net-(Q5-D)") (class "Default")
      (node (ref "Q5") (pin "2") (pinfunction "D_2") (pintype "passive"))
      (node (ref "U7") (pin "3") (pinfunction "~{Inhibit}_3") (pintype "power_in"))
    )
    (net (code "34") (name "Net-(R19-+)") (class "Default")
      (node (ref "R19") (pin "3") (pinfunction "+_3") (pintype "passive"))
      (node (ref "U5") (pin "4") (pinfunction "Adjust_4") (pintype "power_in"))
    )
    (net (code "35") (name "Net-(R19--)") (class "Default")
      (node (ref "R19") (pin "1") (pinfunction "-_1") (pintype "passive"))
      (node (ref "R19") (pin "2") (pinfunction "W_2") (pintype "passive"))
      (node (ref "R20") (pin "1") (pinfunction "-_1") (pintype "passive"))
    )
    (net (code "36") (name "Net-(R20-+)") (class "Default")
      (node (ref "R20") (pin "2") (pinfunction "W_2") (pintype "passive"))
      (node (ref "R20") (pin "3") (pinfunction "+_3") (pintype "passive"))
      (node (ref "R23") (pin "2") (pinfunction "2_2") (pintype "passive"))
    )
    (net (code "37") (name "Net-(R21-+)") (class "Default")
      (node (ref "R21") (pin "3") (pinfunction "+_3") (pintype "passive"))
      (node (ref "U6") (pin "4") (pinfunction "Adjust_4") (pintype "power_in"))
    )
    (net (code "38") (name "Net-(R21--)") (class "Default")
      (node (ref "R21") (pin "1") (pinfunction "-_1") (pintype "passive"))
      (node (ref "R21") (pin "2") (pinfunction "W_2") (pintype "passive"))
      (node (ref "R22") (pin "1") (pinfunction "-_1") (pintype "passive"))
    )
    (net (code "39") (name "Net-(R22-+)") (class "Default")
      (node (ref "R22") (pin "2") (pinfunction "W_2") (pintype "passive"))
      (node (ref "R22") (pin "3") (pinfunction "+_3") (pintype "passive"))
      (node (ref "R24") (pin "2") (pinfunction "2_2") (pintype "passive"))
    )
    (net (code "40") (name "Net-(R25-+)") (class "Default")
      (node (ref "R25") (pin "3") (pinfunction "+_3") (pintype "passive"))
      (node (ref "U7") (pin "4") (pinfunction "Adjust_4") (pintype "power_in"))
    )
    (net (code "41") (name "Net-(R25--)") (class "Default")
      (node (ref "R25") (pin "1") (pinfunction "-_1") (pintype "passive"))
      (node (ref "R25") (pin "2") (pinfunction "W_2") (pintype "passive"))
      (node (ref "R26") (pin "1") (pinfunction "-_1") (pintype "passive"))
    )
    (net (code "42") (name "Net-(R26-+)") (class "Default")
      (node (ref "R26") (pin "2") (pinfunction "W_2") (pintype "passive"))
      (node (ref "R26") (pin "3") (pinfunction "+_3") (pintype "passive"))
      (node (ref "R27") (pin "2") (pinfunction "2_2") (pintype "passive"))
    )
    (net (code "43") (name "Net-(U5-VI)") (class "Default")
      (node (ref "C26") (pin "2") (pinfunction "2_2") (pintype "passive"))
      (node (ref "L7") (pin "2") (pinfunction "2_2") (pintype "passive"))
      (node (ref "U5") (pin "2") (pinfunction "VI_2") (pintype "power_in"))
    )
    (net (code "44") (name "Net-(U6-Sense)") (class "Default")
      (node (ref "C24") (pin "1") (pinfunction "1_1") (pintype "passive"))
      (node (ref "L10") (pin "1") (pinfunction "1_1") (pintype "passive"))
      (node (ref "U6") (pin "5") (pinfunction "Sense_5") (pintype "power_in"))
      (node (ref "U6") (pin "6") (pinfunction "VO_6") (pintype "power_in"))
    )
    (net (code "45") (name "Net-(U6-VI)") (class "Default")
      (node (ref "C28") (pin "2") (pinfunction "2_2") (pintype "passive"))
      (node (ref "L9") (pin "2") (pinfunction "2_2") (pintype "passive"))
      (node (ref "U6") (pin "2") (pinfunction "VI_2") (pintype "power_in"))
    )
    (net (code "46") (name "Net-(U7-Sense)") (class "Default")
      (node (ref "C31") (pin "1") (pinfunction "1_1") (pintype "passive"))
      (node (ref "L12") (pin "1") (pinfunction "1_1") (pintype "passive"))
      (node (ref "U7") (pin "5") (pinfunction "Sense_5") (pintype "power_in"))
      (node (ref "U7") (pin "6") (pinfunction "VO_6") (pintype "power_in"))
    )
    (net (code "47") (name "Net-(U7-VI)") (class "Default")
      (node (ref "C33") (pin "2") (pinfunction "2_2") (pintype "passive"))
      (node (ref "L11") (pin "2") (pinfunction "2_2") (pintype "passive"))
      (node (ref "U7") (pin "2") (pinfunction "VI_2") (pintype "power_in"))
    )
    (net (code "48") (name "Net-(U9-RS)") (class "Default")
      (node (ref "R34") (pin "2") (pinfunction "2_2") (pintype "passive"))
      (node (ref "U9") (pin "8") (pinfunction "RS_8") (pintype "passive"))
    )
    (net (code "49") (name "Net-(U10-A)") (class "Default")
      (node (ref "U10") (pin "2") (pinfunction "A_2") (pintype "input"))
      (node (ref "U11") (pin "3") (pinfunction "PWM2L1/RP23/CN17/PMA0/RC7_3") (pintype "bidirectional"))
    )
    (net (code "50") (name "Net-(U11-AN0{slash}VREF+{slash}CN2{slash}RA0)") (class "Default")
      (node (ref "R35") (pin "1") (pinfunction "1_1") (pintype "passive"))
      (node (ref "R36") (pin "2") (pinfunction "2_2") (pintype "passive"))
      (node (ref "U11") (pin "19") (pinfunction "AN0/VREF+/CN2/RA0_19") (pintype "bidirectional"))
    )
    (net (code "51") (name "Net-(U11-OSCI{slash}CLKI{slash}CN30{slash}RA2)") (class "Default")
      (node (ref "C38") (pin "2") (pinfunction "2_2") (pintype "passive"))
      (node (ref "U11") (pin "30") (pinfunction "OSCI/CLKI/CN30/RA2_30") (pintype "input"))
      (node (ref "Y1") (pin "1") (pinfunction "OSC1_1") (pintype "passive"))
    )
    (net (code "52") (name "Net-(U11-OSCO{slash}CLKO{slash}CN29{slash}RA3)") (class "Default")
      (node (ref "C39") (pin "2") (pinfunction "2_2") (pintype "passive"))
      (node (ref "U11") (pin "31") (pinfunction "OSCO/CLKO/CN29/RA3_31") (pintype "bidirectional"))
      (node (ref "Y1") (pin "2") (pinfunction "OSC2_2") (pintype "passive"))
    )
    (net (code "53") (name "Net-(U11-PWM2H1{slash}RP22{slash}CN18{slash}PMA1{slash}RC6)") (class "Default")
      (node (ref "U11") (pin "2") (pinfunction "PWM2H1/RP22/CN18/PMA1/RC6_2") (pintype "bidirectional"))
      (node (ref "U8") (pin "2") (pinfunction "A_2") (pintype "input"))
    )
    (net (code "54") (name "Net-(U11-RP24{slash}CN20{slash}PMA5{slash}RC8)") (class "Default")
      (node (ref "U11") (pin "4") (pinfunction "RP24/CN20/PMA5/RC8_4") (pintype "bidirectional"))
      (node (ref "U12") (pin "2") (pinfunction "A_2") (pintype "input"))
    )
    (net (code "55") (name "Net-(U11-RP25{slash}CN19{slash}PMA6{slash}RC9)") (class "Default")
      (node (ref "U11") (pin "5") (pinfunction "RP25/CN19/PMA6/RC9_5") (pintype "bidirectional"))
      (node (ref "U14") (pin "2") (pinfunction "A_2") (pintype "input"))
    )
    (net (code "56") (name "Net-(U11-SDA1{slash}RP9{slash}CN21{slash}PMD3{slash}RB9)") (class "Default")
      (node (ref "U11") (pin "1") (pinfunction "SDA1/RP9/CN21/PMD3/RB9_1") (pintype "bidirectional"))
      (node (ref "U13") (pin "2") (pinfunction "A_2") (pintype "input"))
    )
    (net (code "57") (name "Net-(U11-TCK{slash}PMA7{slash}RA7)") (class "Default")
      (node (ref "R42") (pin "2") (pinfunction "2_2") (pintype "passive"))
      (node (ref "U11") (pin "13") (pinfunction "TCK/PMA7/RA7_13") (pintype "bidirectional"))
    )
    (net (code "58") (name "Net-(U11-TDI{slash}PMA9{slash}RA9)") (class "Default")
      (node (ref "R40") (pin "2") (pinfunction "2_2") (pintype "passive"))
      (node (ref "U11") (pin "35") (pinfunction "TDI/PMA9/RA9_35") (pintype "bidirectional"))
    )
    (net (code "59") (name "Net-(U11-TDO{slash}PMA8{slash}RA8)") (class "Default")
      (node (ref "R41") (pin "2") (pinfunction "2_2") (pintype "passive"))
      (node (ref "U11") (pin "32") (pinfunction "TDO/PMA8/RA8_32") (pintype "bidirectional"))
    )
    (net (code "60") (name "Net-(U11-TMS{slash}PMA10{slash}RA10)") (class "Default")
      (node (ref "R39") (pin "2") (pinfunction "2_2") (pintype "passive"))
      (node (ref "U11") (pin "12") (pinfunction "TMS/PMA10/RA10_12") (pintype "bidirectional"))
    )
    (net (code "61") (name "Net-(U11-VCAP{slash}VDDCORE)") (class "Default")
      (node (ref "C40") (pin "1") (pinfunction "1_1") (pintype "passive"))
      (node (ref "U11") (pin "7") (pinfunction "VCAP/VDDCORE_7") (pintype "power_in"))
    )
    (net (code "62") (name "Net-(W1-C2)") (class "Default")
      (node (ref "P5") (pin "5") (pinfunction "5_5") (pintype "passive"))
      (node (ref "W1") (pin "2") (pinfunction "C2_2") (pintype "passive"))
    )
    (net (code "63") (name "VBAT") (class "Default")
      (node (ref "C20") (pin "2") (pinfunction "2_2") (pintype "passive"))
      (node (ref "L7") (pin "1") (pinfunction "1_1") (pintype "passive"))
      (node (ref "P10") (pin "2") (pinfunction "2_2") (pintype "passive"))
      (node (ref "R35") (pin "2") (pinfunction "2_2") (pintype "passive"))
      (node (ref "R38") (pin "2") (pinfunction "2_2") (pintype "passive"))
    )
    (net (code "64") (name "VBAT2") (class "Default")
      (node (ref "C21") (pin "2") (pinfunction "2_2") (pintype "passive"))
      (node (ref "C30") (pin "2") (pinfunction "2_2") (pintype "passive"))
      (node (ref "L11") (pin "1") (pinfunction "1_1") (pintype "passive"))
      (node (ref "L9") (pin "1") (pinfunction "1_1") (pintype "passive"))
      (node (ref "P11") (pin "2") (pinfunction "2_2") (pintype "passive"))
      (node (ref "R37") (pin "2") (pinfunction "2_2") (pintype "passive"))
    )
    (net (code "65") (name "VCC") (class "Default")
      (node (ref "C35") (pin "2") (pinfunction "2_2") (pintype "passive"))
      (node (ref "F4") (pin "2") (pinfunction "2_2") (pintype "passive"))
      (node (ref "P5") (pin "1") (pinfunction "1_1") (pintype "passive"))
      (node (ref "R17") (pin "2") (pinfunction "2_2") (pintype "passive"))
      (node (ref "U9") (pin "3") (pinfunction "VDD_3") (pintype "power_in"))
    )
    (net (code "66") (name "VDD1") (class "Default")
      (node (ref "F6") (pin "2") (pinfunction "2_2") (pintype "passive"))
      (node (ref "P6") (pin "7") (pinfunction "7_7") (pintype "passive"))
      (node (ref "P6") (pin "9") (pinfunction "9_9") (pintype "passive"))
      (node (ref "R29") (pin "2") (pinfunction "2_2") (pintype "passive"))
      (node (ref "R31") (pin "2") (pinfunction "2_2") (pintype "passive"))
    )
    (net (code "67") (name "VDD2") (class "Default")
      (node (ref "F5") (pin "2") (pinfunction "2_2") (pintype "passive"))
      (node (ref "P6") (pin "11") (pinfunction "11_11") (pintype "passive"))
      (node (ref "P6") (pin "13") (pinfunction "13_13") (pintype "passive"))
      (node (ref "R28") (pin "2") (pinfunction "2_2") (pintype "passive"))
      (node (ref "R30") (pin "2") (pinfunction "2_2") (pintype "passive"))
    )
    (net (code "68") (name "unconnected-(P5-Pad7)") (class "Default")
      (node (ref "P5") (pin "7") (pinfunction "7_7") (pintype "passive+no_connect"))
    )
    (net (code "69") (name "unconnected-(P5-Pad8)") (class "Default")
      (node (ref "P5") (pin "8") (pinfunction "8_8") (pintype "passive"))
    )
    (net (code "70") (name "unconnected-(P5-Pad9)") (class "Default")
      (node (ref "P5") (pin "9") (pinfunction "9_9") (pintype "passive+no_connect"))
    )
    (net (code "71") (name "unconnected-(P5-Pad11)") (class "Default")
      (node (ref "P5") (pin "11") (pinfunction "11_11") (pintype "passive+no_connect"))
    )
    (net (code "72") (name "unconnected-(P5-Pad13)") (class "Default")
      (node (ref "P5") (pin "13") (pinfunction "13_13") (pintype "passive+no_connect"))
    )
    (net (code "73") (name "unconnected-(P5-Pad15)") (class "Default")
      (node (ref "P5") (pin "15") (pinfunction "15_15") (pintype "passive+no_connect"))
    )
    (net (code "74") (name "unconnected-(P5-Pad17)") (class "Default")
      (node (ref "P5") (pin "17") (pinfunction "17_17") (pintype "passive+no_connect"))
    )
    (net (code "75") (name "unconnected-(P5-Pad19)") (class "Default")
      (node (ref "P5") (pin "19") (pinfunction "19_19") (pintype "passive+no_connect"))
    )
    (net (code "76") (name "unconnected-(P5-Pad21)") (class "Default")
      (node (ref "P5") (pin "21") (pinfunction "21_21") (pintype "passive+no_connect"))
    )
    (net (code "77") (name "unconnected-(P5-Pad23)") (class "Default")
      (node (ref "P5") (pin "23") (pinfunction "23_23") (pintype "passive+no_connect"))
    )
    (net (code "78") (name "unconnected-(P5-Pad25)") (class "Default")
      (node (ref "P5") (pin "25") (pinfunction "25_25") (pintype "passive+no_connect"))
    )
    (net (code "79") (name "unconnected-(P6-Pad1)") (class "Default")
      (node (ref "P6") (pin "1") (pinfunction "1_1") (pintype "passive+no_connect"))
    )
    (net (code "80") (name "unconnected-(P6-Pad2)") (class "Default")
      (node (ref "P6") (pin "2") (pinfunction "2_2") (pintype "passive+no_connect"))
    )
    (net (code "81") (name "unconnected-(P6-Pad3)") (class "Default")
      (node (ref "P6") (pin "3") (pinfunction "3_3") (pintype "passive+no_connect"))
    )
    (net (code "82") (name "unconnected-(P6-Pad4)") (class "Default")
      (node (ref "P6") (pin "4") (pinfunction "4_4") (pintype "passive+no_connect"))
    )
    (net (code "83") (name "unconnected-(P6-Pad5)") (class "Default")
      (node (ref "P6") (pin "5") (pinfunction "5_5") (pintype "passive+no_connect"))
    )
    (net (code "84") (name "unconnected-(P6-Pad6)") (class "Default")
      (node (ref "P6") (pin "6") (pinfunction "6_6") (pintype "passive+no_connect"))
    )
    (net (code "85") (name "unconnected-(P6-Pad15)") (class "Default")
      (node (ref "P6") (pin "15") (pinfunction "15_15") (pintype "passive+no_connect"))
    )
    (net (code "86") (name "unconnected-(P6-Pad17)") (class "Default")
      (node (ref "P6") (pin "17") (pinfunction "17_17") (pintype "passive+no_connect"))
    )
    (net (code "87") (name "unconnected-(P6-Pad19)") (class "Default")
      (node (ref "P6") (pin "19") (pinfunction "19_19") (pintype "passive+no_connect"))
    )
    (net (code "88") (name "unconnected-(P6-Pad21)") (class "Default")
      (node (ref "P6") (pin "21") (pinfunction "21_21") (pintype "passive+no_connect"))
    )
    (net (code "89") (name "unconnected-(P6-Pad23)") (class "Default")
      (node (ref "P6") (pin "23") (pinfunction "23_23") (pintype "passive+no_connect"))
    )
    (net (code "90") (name "unconnected-(P6-Pad25)") (class "Default")
      (node (ref "P6") (pin "25") (pinfunction "25_25") (pintype "passive+no_connect"))
    )
    (net (code "91") (name "unconnected-(U5-~{Inhibit}-Pad3)") (class "Default")
      (node (ref "U5") (pin "3") (pinfunction "~{Inhibit}_3") (pintype "power_in+no_connect"))
    )
    (net (code "92") (name "unconnected-(U9-VREF-Pad5)") (class "Default")
      (node (ref "U9") (pin "5") (pinfunction "VREF_5") (pintype "output+no_connect"))
    )
    (net (code "93") (name "unconnected-(U11-AN1{slash}VREF-{slash}CN3{slash}RA1-Pad20)") (class "Default")
      (node (ref "U11") (pin "20") (pinfunction "AN1/VREF-/CN3/RA1_20") (pintype "bidirectional+no_connect"))
    )
    (net (code "94") (name "unconnected-(U11-AN6{slash}DAC1RM{slash}RP16{slash}CN8{slash}RC0-Pad25)") (class "Default")
      (node (ref "U11") (pin "25") (pinfunction "AN6/DAC1RM/RP16/CN8/RC0_25") (pintype "bidirectional+no_connect"))
    )
    (net (code "95") (name "unconnected-(U11-AN7{slash}DAC1LM{slash}RP17{slash}CN9{slash}RC1-Pad26)") (class "Default")
      (node (ref "U11") (pin "26") (pinfunction "AN7/DAC1LM/RP17/CN9/RC1_26") (pintype "bidirectional+no_connect"))
    )
    (net (code "96") (name "unconnected-(U11-AN8{slash}CVREF{slash}RP18{slash}PMA2{slash}CN10{slash}RC2-Pad27)") (class "Default")
      (node (ref "U11") (pin "27") (pinfunction "AN8/CVREF/RP18/PMA2/CN10/RC2_27") (pintype "bidirectional+no_connect"))
    )
    (net (code "97") (name "unconnected-(U11-PGD3{slash}EMUD3{slash}ASDA1{slash}RP5{slash}CN27{slash}PMD7{slash}RB5-Pad41)") (class "Default")
      (node (ref "U11") (pin "41") (pinfunction "PGD3/EMUD3/ASDA1/RP5/CN27/PMD7/RB5_41") (pintype "bidirectional+no_connect"))
    )
    (net (code "98") (name "unconnected-(U11-PWM1H1{slash}DAC1LP{slash}RTCC{slash}RP14{slash}CN12{slash}PMWR{slash}RB14-Pad14)") (class "Default")
      (node (ref "U11") (pin "14") (pinfunction "PWM1H1/DAC1LP/RTCC/RP14/CN12/PMWR/RB14_14") (pintype "bidirectional+no_connect"))
    )
    (net (code "99") (name "unconnected-(U11-PWM1H2{slash}DAC1RP{slash}RP12{slash}CN14{slash}PMD0{slash}RB12-Pad10)") (class "Default")
      (node (ref "U11") (pin "10") (pinfunction "PWM1H2/DAC1RP/RP12/CN14/PMD0/RB12_10") (pintype "bidirectional+no_connect"))
    )
    (net (code "100") (name "unconnected-(U11-PWM1L2{slash}DAC1RN{slash}RP13{slash}CN13{slash}PMRD{slash}RB13-Pad11)") (class "Default")
      (node (ref "U11") (pin "11") (pinfunction "PWM1L2/DAC1RN/RP13/CN13/PMRD/RB13_11") (pintype "bidirectional+no_connect"))
    )
    (net (code "101") (name "unconnected-(U11-RP19{slash}CN28{slash}PMBE{slash}RC3-Pad36)") (class "Default")
      (node (ref "U11") (pin "36") (pinfunction "RP19/CN28/PMBE/RC3_36") (pintype "bidirectional+no_connect"))
    )
    (net (code "102") (name "unconnected-(U11-RP20{slash}CN25{slash}PMA4{slash}RC4-Pad37)") (class "Default")
      (node (ref "U11") (pin "37") (pinfunction "RP20/CN25/PMA4/RC4_37") (pintype "bidirectional+no_connect"))
    )
    (net (code "103") (name "unconnected-(U11-RP21{slash}CN26{slash}PMA3{slash}RC5-Pad38)") (class "Default")
      (node (ref "U11") (pin "38") (pinfunction "RP21/CN26/PMA3/RC5_38") (pintype "bidirectional"))
    )
    (net (code "104") (name "unconnected-(U11-SCL1{slash}RP8{slash}CN22{slash}PMD4{slash}RB8-Pad44)") (class "Default")
      (node (ref "U11") (pin "44") (pinfunction "SCL1/RP8/CN22/PMD4/RB8_44") (pintype "bidirectional+no_connect"))
    )
  )
)
